# MODULO_LEDS.net
KiCad netlist of a schematic drawn in EAGLE
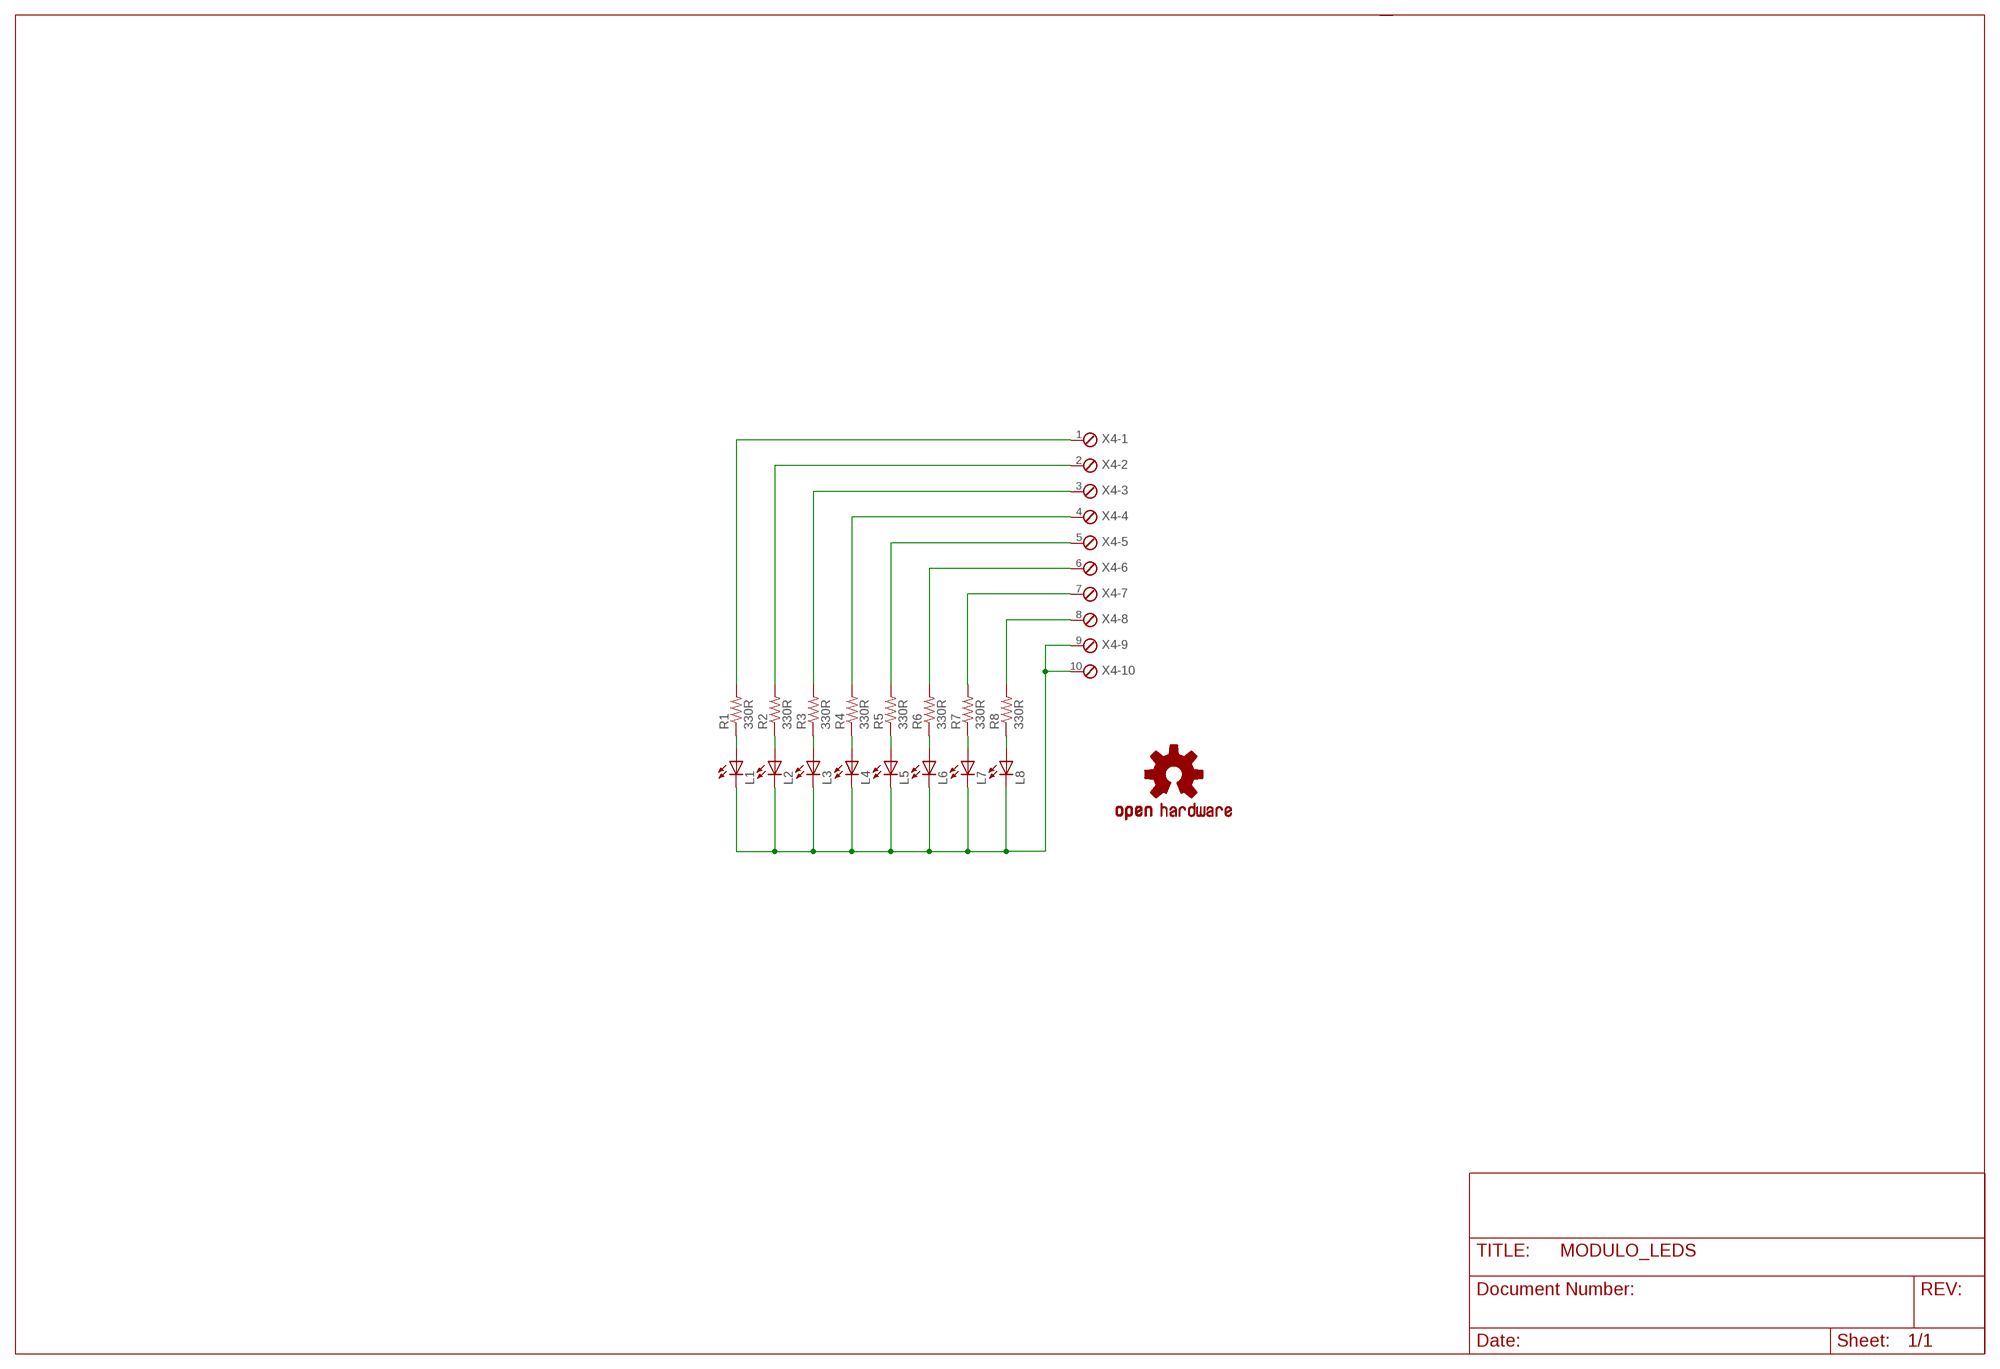
[diagram p0: schematic, sheet 1]

(export (version "E")
  (design (tool "Eeschema 10.0.6"))
  (components
    (comp (ref "L1")
      (value "LED3MM")
      (footprint "eagle-import:LED3MM")
      (libsource (lib "eagle-import") (part "LED3MM"))
    )
    (comp (ref "L2")
      (value "LED3MM")
      (footprint "eagle-import:LED3MM")
      (libsource (lib "eagle-import") (part "LED3MM"))
    )
    (comp (ref "L3")
      (value "LED3MM")
      (footprint "eagle-import:LED3MM")
      (libsource (lib "eagle-import") (part "LED3MM"))
    )
    (comp (ref "L4")
      (value "LED3MM")
      (footprint "eagle-import:LED3MM")
      (libsource (lib "eagle-import") (part "LED3MM"))
    )
    (comp (ref "L5")
      (value "LED3MM")
      (footprint "eagle-import:LED3MM")
      (libsource (lib "eagle-import") (part "LED3MM"))
    )
    (comp (ref "L6")
      (value "LED3MM")
      (footprint "eagle-import:LED3MM")
      (libsource (lib "eagle-import") (part "LED3MM"))
    )
    (comp (ref "L7")
      (value "LED3MM")
      (footprint "eagle-import:LED3MM")
      (libsource (lib "eagle-import") (part "LED3MM"))
    )
    (comp (ref "L8")
      (value "LED3MM")
      (footprint "eagle-import:LED3MM")
      (libsource (lib "eagle-import") (part "LED3MM"))
    )
    (comp (ref "LOGO1")
      (value "OSHW-LOGOM")
      (footprint "eagle-import:OSHW-LOGO-M")
      (libsource (lib "eagle-import") (part "OSHW-LOGOM"))
    )
    (comp (ref "R1")
      (value "330R")
      (footprint "eagle-import:AXIAL-0.4")
      (libsource (lib "eagle-import") (part "RESISTORPTH-1/4W"))
    )
    (comp (ref "R2")
      (value "330R")
      (footprint "eagle-import:AXIAL-0.4")
      (libsource (lib "eagle-import") (part "RESISTORPTH-1/4W"))
    )
    (comp (ref "R3")
      (value "330R")
      (footprint "eagle-import:AXIAL-0.4")
      (libsource (lib "eagle-import") (part "RESISTORPTH-1/4W"))
    )
    (comp (ref "R4")
      (value "330R")
      (footprint "eagle-import:AXIAL-0.4")
      (libsource (lib "eagle-import") (part "RESISTORPTH-1/4W"))
    )
    (comp (ref "R5")
      (value "330R")
      (footprint "eagle-import:AXIAL-0.4")
      (libsource (lib "eagle-import") (part "RESISTORPTH-1/4W"))
    )
    (comp (ref "R6")
      (value "330R")
      (footprint "eagle-import:AXIAL-0.4")
      (libsource (lib "eagle-import") (part "RESISTORPTH-1/4W"))
    )
    (comp (ref "R7")
      (value "330R")
      (footprint "eagle-import:AXIAL-0.4")
      (libsource (lib "eagle-import") (part "RESISTORPTH-1/4W"))
    )
    (comp (ref "R8")
      (value "330R")
      (footprint "eagle-import:AXIAL-0.4")
      (libsource (lib "eagle-import") (part "RESISTORPTH-1/4W"))
    )
    (comp (ref "X4")
      (value "MPT10")
      (footprint "eagle-import:10POL254")
      (libsource (lib "eagle-import") (part "MPT10"))
    )
  )
  (nets
    (net (code "1") (name "Net-(L1-C)") (class "Default")
      (node (ref "L1") (pin "K") (pinfunction "C_K") (pintype "passive"))
      (node (ref "L2") (pin "K") (pinfunction "C_K") (pintype "passive"))
      (node (ref "L3") (pin "K") (pinfunction "C_K") (pintype "passive"))
      (node (ref "L4") (pin "K") (pinfunction "C_K") (pintype "passive"))
      (node (ref "L5") (pin "K") (pinfunction "C_K") (pintype "passive"))
      (node (ref "L6") (pin "K") (pinfunction "C_K") (pintype "passive"))
      (node (ref "L7") (pin "K") (pinfunction "C_K") (pintype "passive"))
      (node (ref "L8") (pin "K") (pinfunction "C_K") (pintype "passive"))
      (node (ref "X4") (pin "10") (pinfunction "1_10") (pintype "passive"))
      (node (ref "X4") (pin "9") (pinfunction "1_9") (pintype "passive"))
    )
    (net (code "2") (name "Net-(R1-1)") (class "Default")
      (node (ref "L1") (pin "A") (pinfunction "A_A") (pintype "passive"))
      (node (ref "R1") (pin "P$1") (pinfunction "1_P$1") (pintype "passive"))
    )
    (net (code "3") (name "Net-(R1-2)") (class "Default")
      (node (ref "R1") (pin "P$2") (pinfunction "2_P$2") (pintype "passive"))
      (node (ref "X4") (pin "1") (pinfunction "1_1") (pintype "passive"))
    )
    (net (code "4") (name "Net-(R2-1)") (class "Default")
      (node (ref "L2") (pin "A") (pinfunction "A_A") (pintype "passive"))
      (node (ref "R2") (pin "P$1") (pinfunction "1_P$1") (pintype "passive"))
    )
    (net (code "5") (name "Net-(R2-2)") (class "Default")
      (node (ref "R2") (pin "P$2") (pinfunction "2_P$2") (pintype "passive"))
      (node (ref "X4") (pin "2") (pinfunction "1_2") (pintype "passive"))
    )
    (net (code "6") (name "Net-(R3-1)") (class "Default")
      (node (ref "L3") (pin "A") (pinfunction "A_A") (pintype "passive"))
      (node (ref "R3") (pin "P$1") (pinfunction "1_P$1") (pintype "passive"))
    )
    (net (code "7") (name "Net-(R3-2)") (class "Default")
      (node (ref "R3") (pin "P$2") (pinfunction "2_P$2") (pintype "passive"))
      (node (ref "X4") (pin "3") (pinfunction "1_3") (pintype "passive"))
    )
    (net (code "8") (name "Net-(R4-1)") (class "Default")
      (node (ref "L4") (pin "A") (pinfunction "A_A") (pintype "passive"))
      (node (ref "R4") (pin "P$1") (pinfunction "1_P$1") (pintype "passive"))
    )
    (net (code "9") (name "Net-(R4-2)") (class "Default")
      (node (ref "R4") (pin "P$2") (pinfunction "2_P$2") (pintype "passive"))
      (node (ref "X4") (pin "4") (pinfunction "1_4") (pintype "passive"))
    )
    (net (code "10") (name "Net-(R5-1)") (class "Default")
      (node (ref "L5") (pin "A") (pinfunction "A_A") (pintype "passive"))
      (node (ref "R5") (pin "P$1") (pinfunction "1_P$1") (pintype "passive"))
    )
    (net (code "11") (name "Net-(R5-2)") (class "Default")
      (node (ref "R5") (pin "P$2") (pinfunction "2_P$2") (pintype "passive"))
      (node (ref "X4") (pin "5") (pinfunction "1_5") (pintype "passive"))
    )
    (net (code "12") (name "Net-(R6-1)") (class "Default")
      (node (ref "L6") (pin "A") (pinfunction "A_A") (pintype "passive"))
      (node (ref "R6") (pin "P$1") (pinfunction "1_P$1") (pintype "passive"))
    )
    (net (code "13") (name "Net-(R6-2)") (class "Default")
      (node (ref "R6") (pin "P$2") (pinfunction "2_P$2") (pintype "passive"))
      (node (ref "X4") (pin "6") (pinfunction "1_6") (pintype "passive"))
    )
    (net (code "14") (name "Net-(R7-1)") (class "Default")
      (node (ref "L7") (pin "A") (pinfunction "A_A") (pintype "passive"))
      (node (ref "R7") (pin "P$1") (pinfunction "1_P$1") (pintype "passive"))
    )
    (net (code "15") (name "Net-(R7-2)") (class "Default")
      (node (ref "R7") (pin "P$2") (pinfunction "2_P$2") (pintype "passive"))
      (node (ref "X4") (pin "7") (pinfunction "1_7") (pintype "passive"))
    )
    (net (code "16") (name "Net-(R8-1)") (class "Default")
      (node (ref "L8") (pin "A") (pinfunction "A_A") (pintype "passive"))
      (node (ref "R8") (pin "P$1") (pinfunction "1_P$1") (pintype "passive"))
    )
    (net (code "17") (name "Net-(R8-2)") (class "Default")
      (node (ref "R8") (pin "P$2") (pinfunction "2_P$2") (pintype "passive"))
      (node (ref "X4") (pin "8") (pinfunction "1_8") (pintype "passive"))
    )
  )
)
